# daughterboard.net
KiCad netlist of a schematic drawn in EAGLE
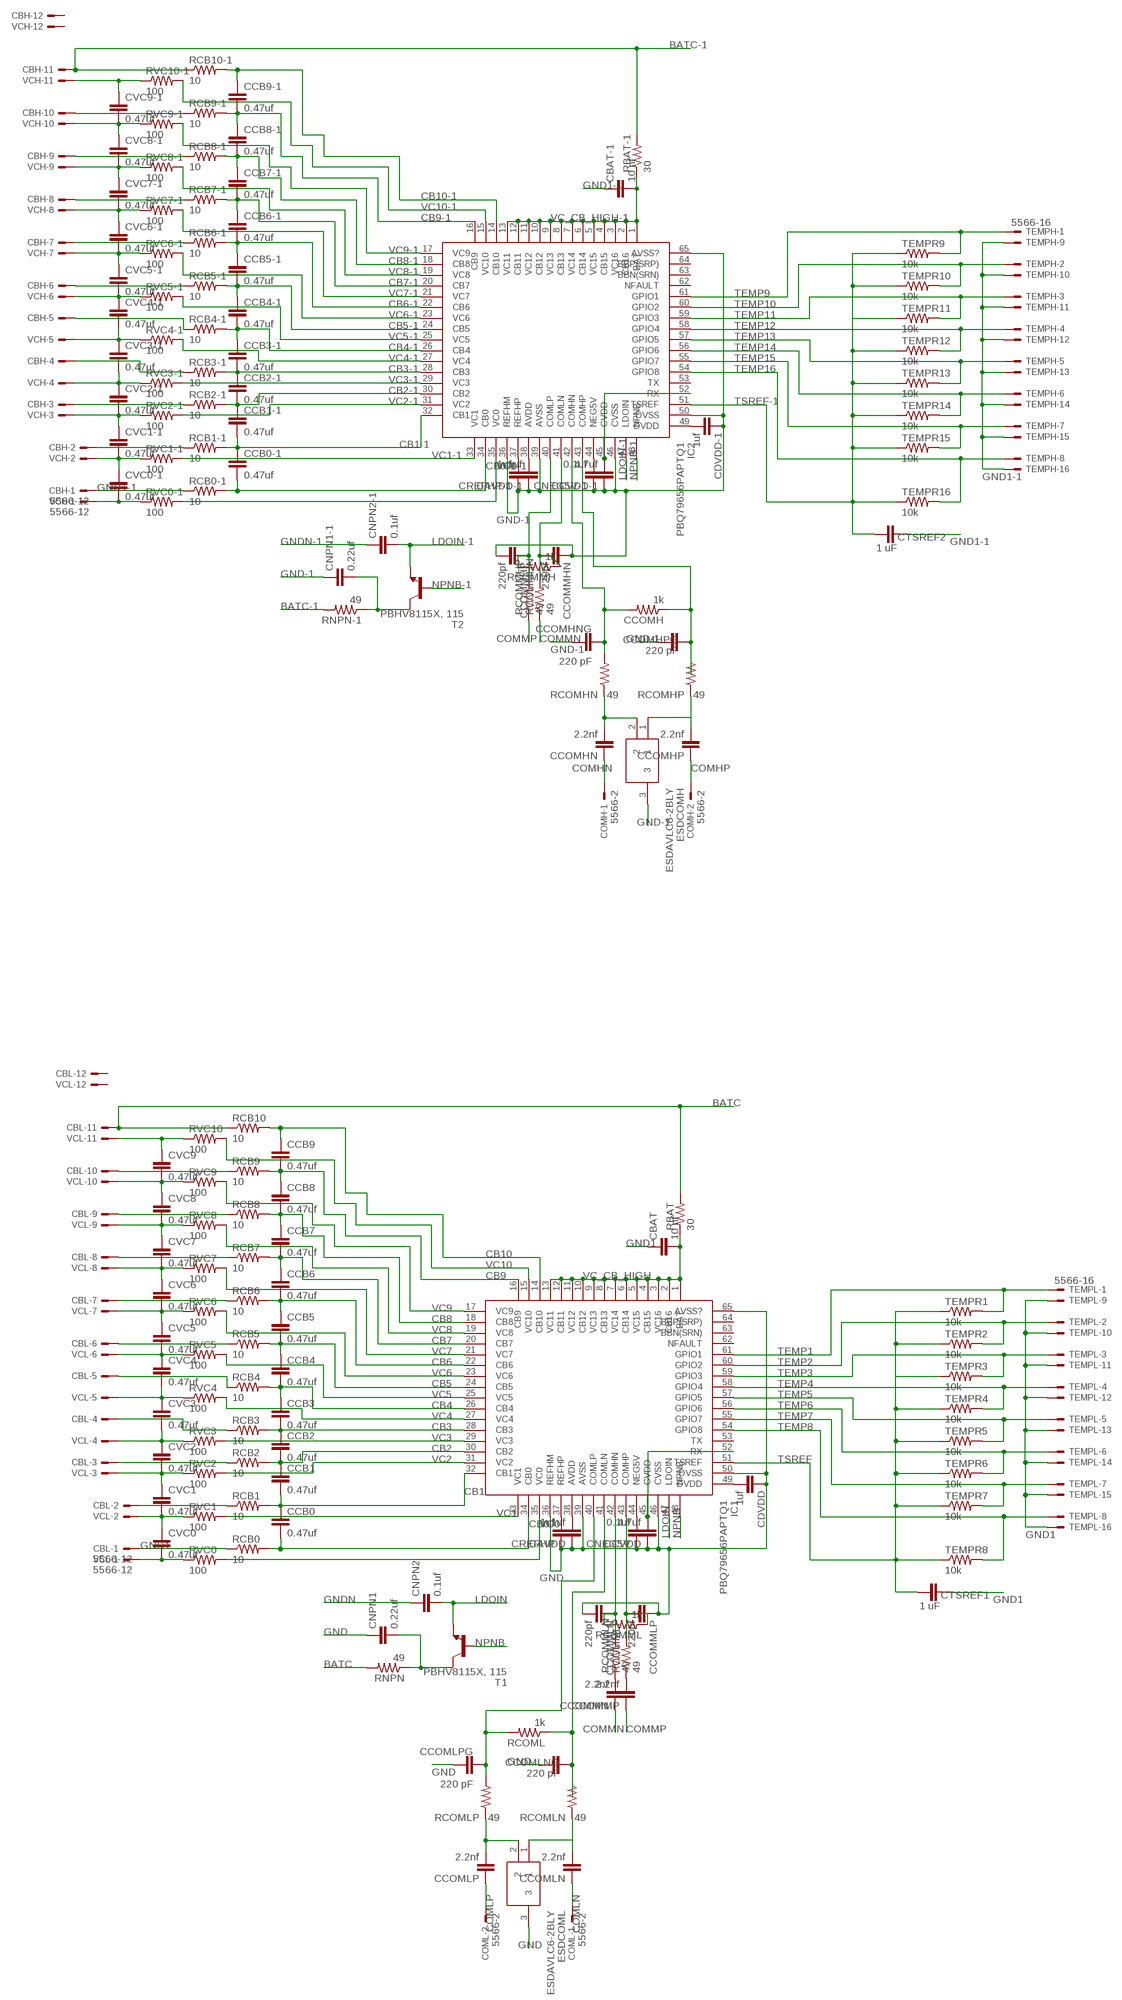
[diagram p0: schematic, sheet 1]

(export (version "E")
  (design (tool "Eeschema 10.0.6"))
  (components
    (comp (ref "CAVDD")
      (value "1uf")
      (footprint "eagle-import:C0603")
      (libsource (lib "eagle-import") (part "C-EUC0603"))
    )
    (comp (ref "CAVDD-1")
      (value "1uf")
      (footprint "eagle-import:C0603")
      (libsource (lib "eagle-import") (part "C-EUC0603"))
    )
    (comp (ref "CBAT")
      (value "10 nf")
      (footprint "eagle-import:C0603")
      (libsource (lib "eagle-import") (part "C-EUC0603"))
    )
    (comp (ref "CBAT-1")
      (value "10 nf")
      (footprint "eagle-import:C0603")
      (libsource (lib "eagle-import") (part "C-EUC0603"))
    )
    (comp (ref "CBH")
      (value "5566-12")
      (footprint "eagle-import:5566-12")
      (fields (field (name "MF") "MOLEX"))
      (libsource (lib "eagle-import") (part "5566-12"))
    )
    (comp (ref "CBL")
      (value "5566-12")
      (footprint "eagle-import:5566-12")
      (fields (field (name "MF") "MOLEX"))
      (libsource (lib "eagle-import") (part "5566-12"))
    )
    (comp (ref "CCB0")
      (value "0.47uf")
      (footprint "eagle-import:C0603")
      (libsource (lib "eagle-import") (part "C-EUC0603"))
    )
    (comp (ref "CCB0-1")
      (value "0.47uf")
      (footprint "eagle-import:C0603")
      (libsource (lib "eagle-import") (part "C-EUC0603"))
    )
    (comp (ref "CCB1")
      (value "0.47uf")
      (footprint "eagle-import:C0603")
      (libsource (lib "eagle-import") (part "C-EUC0603"))
    )
    (comp (ref "CCB1-1")
      (value "0.47uf")
      (footprint "eagle-import:C0603")
      (libsource (lib "eagle-import") (part "C-EUC0603"))
    )
    (comp (ref "CCB2")
      (value "0.47uf")
      (footprint "eagle-import:C0603")
      (libsource (lib "eagle-import") (part "C-EUC0603"))
    )
    (comp (ref "CCB2-1")
      (value "0.47uf")
      (footprint "eagle-import:C0603")
      (libsource (lib "eagle-import") (part "C-EUC0603"))
    )
    (comp (ref "CCB3")
      (value "0.47uf")
      (footprint "eagle-import:C0603")
      (libsource (lib "eagle-import") (part "C-EUC0603"))
    )
    (comp (ref "CCB3-1")
      (value "0.47uf")
      (footprint "eagle-import:C0603")
      (libsource (lib "eagle-import") (part "C-EUC0603"))
    )
    (comp (ref "CCB4")
      (value "0.47uf")
      (footprint "eagle-import:C0603")
      (libsource (lib "eagle-import") (part "C-EUC0603"))
    )
    (comp (ref "CCB4-1")
      (value "0.47uf")
      (footprint "eagle-import:C0603")
      (libsource (lib "eagle-import") (part "C-EUC0603"))
    )
    (comp (ref "CCB5")
      (value "0.47uf")
      (footprint "eagle-import:C0603")
      (libsource (lib "eagle-import") (part "C-EUC0603"))
    )
    (comp (ref "CCB5-1")
      (value "0.47uf")
      (footprint "eagle-import:C0603")
      (libsource (lib "eagle-import") (part "C-EUC0603"))
    )
    (comp (ref "CCB6")
      (value "0.47uf")
      (footprint "eagle-import:C0603")
      (libsource (lib "eagle-import") (part "C-EUC0603"))
    )
    (comp (ref "CCB6-1")
      (value "0.47uf")
      (footprint "eagle-import:C0603")
      (libsource (lib "eagle-import") (part "C-EUC0603"))
    )
    (comp (ref "CCB7")
      (value "0.47uf")
      (footprint "eagle-import:C0603")
      (libsource (lib "eagle-import") (part "C-EUC0603"))
    )
    (comp (ref "CCB7-1")
      (value "0.47uf")
      (footprint "eagle-import:C0603")
      (libsource (lib "eagle-import") (part "C-EUC0603"))
    )
    (comp (ref "CCB8")
      (value "0.47uf")
      (footprint "eagle-import:C0603")
      (libsource (lib "eagle-import") (part "C-EUC0603"))
    )
    (comp (ref "CCB8-1")
      (value "0.47uf")
      (footprint "eagle-import:C0603")
      (libsource (lib "eagle-import") (part "C-EUC0603"))
    )
    (comp (ref "CCB9")
      (value "0.47uf")
      (footprint "eagle-import:C0603")
      (libsource (lib "eagle-import") (part "C-EUC0603"))
    )
    (comp (ref "CCB9-1")
      (value "0.47uf")
      (footprint "eagle-import:C0603")
      (libsource (lib "eagle-import") (part "C-EUC0603"))
    )
    (comp (ref "CCOMH")
      (value "1k")
      (footprint "eagle-import:R0603")
      (libsource (lib "eagle-import") (part "R-US_R0603"))
    )
    (comp (ref "CCOMHN")
      (value "2.2nf")
      (footprint "eagle-import:C0603")
      (libsource (lib "eagle-import") (part "C-EUC0603"))
    )
    (comp (ref "CCOMHNG")
      (value "220 pF")
      (footprint "eagle-import:C0603")
      (libsource (lib "eagle-import") (part "C-EUC0603"))
    )
    (comp (ref "CCOMHP")
      (value "2.2nf")
      (footprint "eagle-import:C0603")
      (libsource (lib "eagle-import") (part "C-EUC0603"))
    )
    (comp (ref "CCOMHPG")
      (value "220 pF")
      (footprint "eagle-import:C0603")
      (libsource (lib "eagle-import") (part "C-EUC0603"))
    )
    (comp (ref "CCOMLN")
      (value "2.2nf")
      (footprint "eagle-import:C0603")
      (libsource (lib "eagle-import") (part "C-EUC0603"))
    )
    (comp (ref "CCOMLNG")
      (value "220 pF")
      (footprint "eagle-import:C0603")
      (libsource (lib "eagle-import") (part "C-EUC0603"))
    )
    (comp (ref "CCOMLP")
      (value "2.2nf")
      (footprint "eagle-import:C0603")
      (libsource (lib "eagle-import") (part "C-EUC0603"))
    )
    (comp (ref "CCOMLPG")
      (value "220 pF")
      (footprint "eagle-import:C0603")
      (libsource (lib "eagle-import") (part "C-EUC0603"))
    )
    (comp (ref "CCOMMHN")
      (value "220pf")
      (footprint "eagle-import:C0603")
      (libsource (lib "eagle-import") (part "C-EUC0603"))
    )
    (comp (ref "CCOMMHP")
      (value "220pf")
      (footprint "eagle-import:C0603")
      (libsource (lib "eagle-import") (part "C-EUC0603"))
    )
    (comp (ref "CCOMMLN")
      (value "220pf")
      (footprint "eagle-import:C0603")
      (libsource (lib "eagle-import") (part "C-EUC0603"))
    )
    (comp (ref "CCOMMLP")
      (value "220pf")
      (footprint "eagle-import:C0603")
      (libsource (lib "eagle-import") (part "C-EUC0603"))
    )
    (comp (ref "CCOMMN")
      (value "2.2nf")
      (footprint "eagle-import:C0603")
      (libsource (lib "eagle-import") (part "C-EUC0603"))
    )
    (comp (ref "CCOMMP")
      (value "2.2nf")
      (footprint "eagle-import:C0603")
      (libsource (lib "eagle-import") (part "C-EUC0603"))
    )
    (comp (ref "CCVDD")
      (value "4.7uf")
      (footprint "eagle-import:C0603")
      (libsource (lib "eagle-import") (part "C-EUC0603"))
    )
    (comp (ref "CCVDD-1")
      (value "4.7uf")
      (footprint "eagle-import:C0603")
      (libsource (lib "eagle-import") (part "C-EUC0603"))
    )
    (comp (ref "CDVDD")
      (value "1uf")
      (footprint "eagle-import:C0603")
      (libsource (lib "eagle-import") (part "C-EUC0603"))
    )
    (comp (ref "CDVDD-1")
      (value "1uf")
      (footprint "eagle-import:C0603")
      (libsource (lib "eagle-import") (part "C-EUC0603"))
    )
    (comp (ref "CNEG5V")
      (value "0.1uf")
      (footprint "eagle-import:C0603")
      (libsource (lib "eagle-import") (part "C-EUC0603"))
    )
    (comp (ref "CNEG5V-1")
      (value "0.1uf")
      (footprint "eagle-import:C0603")
      (libsource (lib "eagle-import") (part "C-EUC0603"))
    )
    (comp (ref "CNPN1")
      (value "0.22uf")
      (footprint "eagle-import:C0603")
      (libsource (lib "eagle-import") (part "C-EUC0603"))
    )
    (comp (ref "CNPN1-1")
      (value "0.22uf")
      (footprint "eagle-import:C0603")
      (libsource (lib "eagle-import") (part "C-EUC0603"))
    )
    (comp (ref "CNPN2")
      (value "0.1uf")
      (footprint "eagle-import:C0603")
      (libsource (lib "eagle-import") (part "C-EUC0603"))
    )
    (comp (ref "CNPN2-1")
      (value "0.1uf")
      (footprint "eagle-import:C0603")
      (libsource (lib "eagle-import") (part "C-EUC0603"))
    )
    (comp (ref "COMH")
      (value "5566-2")
      (footprint "eagle-import:5566-2")
      (fields (field (name "MF") "MOLEX"))
      (libsource (lib "eagle-import") (part "5566-2"))
    )
    (comp (ref "COML")
      (value "5566-2")
      (footprint "eagle-import:5566-2")
      (fields (field (name "MF") "MOLEX"))
      (libsource (lib "eagle-import") (part "5566-2"))
    )
    (comp (ref "CREFHP")
      (value "1uf")
      (footprint "eagle-import:C0603")
      (libsource (lib "eagle-import") (part "C-EUC0603"))
    )
    (comp (ref "CREFHP-1")
      (value "1uf")
      (footprint "eagle-import:C0603")
      (libsource (lib "eagle-import") (part "C-EUC0603"))
    )
    (comp (ref "CTSREF1")
      (value "1 uF")
      (footprint "eagle-import:C0603")
      (libsource (lib "eagle-import") (part "C-EUC0603"))
    )
    (comp (ref "CTSREF2")
      (value "1 uF")
      (footprint "eagle-import:C0603")
      (libsource (lib "eagle-import") (part "C-EUC0603"))
    )
    (comp (ref "CVC0")
      (value "0.47uf")
      (footprint "eagle-import:C0603")
      (libsource (lib "eagle-import") (part "C-EUC0603"))
    )
    (comp (ref "CVC0-1")
      (value "0.47uf")
      (footprint "eagle-import:C0603")
      (libsource (lib "eagle-import") (part "C-EUC0603"))
    )
    (comp (ref "CVC1")
      (value "0.47uf")
      (footprint "eagle-import:C0603")
      (libsource (lib "eagle-import") (part "C-EUC0603"))
    )
    (comp (ref "CVC1-1")
      (value "0.47uf")
      (footprint "eagle-import:C0603")
      (libsource (lib "eagle-import") (part "C-EUC0603"))
    )
    (comp (ref "CVC2")
      (value "0.47uf")
      (footprint "eagle-import:C0603")
      (libsource (lib "eagle-import") (part "C-EUC0603"))
    )
    (comp (ref "CVC2-1")
      (value "0.47uf")
      (footprint "eagle-import:C0603")
      (libsource (lib "eagle-import") (part "C-EUC0603"))
    )
    (comp (ref "CVC3")
      (value "0.47uf")
      (footprint "eagle-import:C0603")
      (libsource (lib "eagle-import") (part "C-EUC0603"))
    )
    (comp (ref "CVC3-1")
      (value "0.47uf")
      (footprint "eagle-import:C0603")
      (libsource (lib "eagle-import") (part "C-EUC0603"))
    )
    (comp (ref "CVC4")
      (value "0.47uf")
      (footprint "eagle-import:C0603")
      (libsource (lib "eagle-import") (part "C-EUC0603"))
    )
    (comp (ref "CVC4-1")
      (value "0.47uf")
      (footprint "eagle-import:C0603")
      (libsource (lib "eagle-import") (part "C-EUC0603"))
    )
    (comp (ref "CVC5")
      (value "0.47uf")
      (footprint "eagle-import:C0603")
      (libsource (lib "eagle-import") (part "C-EUC0603"))
    )
    (comp (ref "CVC5-1")
      (value "0.47uf")
      (footprint "eagle-import:C0603")
      (libsource (lib "eagle-import") (part "C-EUC0603"))
    )
    (comp (ref "CVC6")
      (value "0.47uf")
      (footprint "eagle-import:C0603")
      (libsource (lib "eagle-import") (part "C-EUC0603"))
    )
    (comp (ref "CVC6-1")
      (value "0.47uf")
      (footprint "eagle-import:C0603")
      (libsource (lib "eagle-import") (part "C-EUC0603"))
    )
    (comp (ref "CVC7")
      (value "0.47uf")
      (footprint "eagle-import:C0603")
      (libsource (lib "eagle-import") (part "C-EUC0603"))
    )
    (comp (ref "CVC7-1")
      (value "0.47uf")
      (footprint "eagle-import:C0603")
      (libsource (lib "eagle-import") (part "C-EUC0603"))
    )
    (comp (ref "CVC8")
      (value "0.47uf")
      (footprint "eagle-import:C0603")
      (libsource (lib "eagle-import") (part "C-EUC0603"))
    )
    (comp (ref "CVC8-1")
      (value "0.47uf")
      (footprint "eagle-import:C0603")
      (libsource (lib "eagle-import") (part "C-EUC0603"))
    )
    (comp (ref "CVC9")
      (value "0.47uf")
      (footprint "eagle-import:C0603")
      (libsource (lib "eagle-import") (part "C-EUC0603"))
    )
    (comp (ref "CVC9-1")
      (value "0.47uf")
      (footprint "eagle-import:C0603")
      (libsource (lib "eagle-import") (part "C-EUC0603"))
    )
    (comp (ref "ESDCOMH")
      (value "ESDAVLC6-2BLY")
      (footprint "eagle-import:SOT95P255X150-3N")
      (fields (field (name "MOUSER_PART_NUMBER") "511-ESDAVLC6-2BLY"))
      (libsource (lib "eagle-import") (part "ESDAVLC6-2BLY"))
    )
    (comp (ref "ESDCOML")
      (value "ESDAVLC6-2BLY")
      (footprint "eagle-import:SOT95P255X150-3N")
      (fields (field (name "MOUSER_PART_NUMBER") "511-ESDAVLC6-2BLY"))
      (libsource (lib "eagle-import") (part "ESDAVLC6-2BLY"))
    )
    (comp (ref "IC1")
      (value "PBQ79656PAPTQ1")
      (footprint "eagle-import:QFP50P1200X1200X120-65N")
      (libsource (lib "eagle-import") (part "PBQ79656PAPTQ1"))
    )
    (comp (ref "IC2")
      (value "PBQ79656PAPTQ1")
      (footprint "eagle-import:QFP50P1200X1200X120-65N")
      (libsource (lib "eagle-import") (part "PBQ79656PAPTQ1"))
    )
    (comp (ref "RBAT")
      (value "30")
      (footprint "eagle-import:R0603")
      (libsource (lib "eagle-import") (part "R-US_R0603"))
    )
    (comp (ref "RBAT-1")
      (value "30")
      (footprint "eagle-import:R0603")
      (libsource (lib "eagle-import") (part "R-US_R0603"))
    )
    (comp (ref "RCB0")
      (value "10")
      (footprint "eagle-import:R1210")
      (libsource (lib "eagle-import") (part "R-US_R1210"))
    )
    (comp (ref "RCB0-1")
      (value "10")
      (footprint "eagle-import:R1210")
      (libsource (lib "eagle-import") (part "R-US_R1210"))
    )
    (comp (ref "RCB1")
      (value "10")
      (footprint "eagle-import:R1210")
      (libsource (lib "eagle-import") (part "R-US_R1210"))
    )
    (comp (ref "RCB1-1")
      (value "10")
      (footprint "eagle-import:R1210")
      (libsource (lib "eagle-import") (part "R-US_R1210"))
    )
    (comp (ref "RCB2")
      (value "10")
      (footprint "eagle-import:R1210")
      (libsource (lib "eagle-import") (part "R-US_R1210"))
    )
    (comp (ref "RCB2-1")
      (value "10")
      (footprint "eagle-import:R1210")
      (libsource (lib "eagle-import") (part "R-US_R1210"))
    )
    (comp (ref "RCB3")
      (value "10")
      (footprint "eagle-import:R1210")
      (libsource (lib "eagle-import") (part "R-US_R1210"))
    )
    (comp (ref "RCB3-1")
      (value "10")
      (footprint "eagle-import:R1210")
      (libsource (lib "eagle-import") (part "R-US_R1210"))
    )
    (comp (ref "RCB4")
      (value "10")
      (footprint "eagle-import:R1210")
      (libsource (lib "eagle-import") (part "R-US_R1210"))
    )
    (comp (ref "RCB4-1")
      (value "10")
      (footprint "eagle-import:R1210")
      (libsource (lib "eagle-import") (part "R-US_R1210"))
    )
    (comp (ref "RCB5")
      (value "10")
      (footprint "eagle-import:R1210")
      (libsource (lib "eagle-import") (part "R-US_R1210"))
    )
    (comp (ref "RCB5-1")
      (value "10")
      (footprint "eagle-import:R1210")
      (libsource (lib "eagle-import") (part "R-US_R1210"))
    )
    (comp (ref "RCB6")
      (value "10")
      (footprint "eagle-import:R1210")
      (libsource (lib "eagle-import") (part "R-US_R1210"))
    )
    (comp (ref "RCB6-1")
      (value "10")
      (footprint "eagle-import:R1210")
      (libsource (lib "eagle-import") (part "R-US_R1210"))
    )
    (comp (ref "RCB7")
      (value "10")
      (footprint "eagle-import:R1210")
      (libsource (lib "eagle-import") (part "R-US_R1210"))
    )
    (comp (ref "RCB7-1")
      (value "10")
      (footprint "eagle-import:R1210")
      (libsource (lib "eagle-import") (part "R-US_R1210"))
    )
    (comp (ref "RCB8")
      (value "10")
      (footprint "eagle-import:R1210")
      (libsource (lib "eagle-import") (part "R-US_R1210"))
    )
    (comp (ref "RCB8-1")
      (value "10")
      (footprint "eagle-import:R1210")
      (libsource (lib "eagle-import") (part "R-US_R1210"))
    )
    (comp (ref "RCB9")
      (value "10")
      (footprint "eagle-import:R1210")
      (libsource (lib "eagle-import") (part "R-US_R1210"))
    )
    (comp (ref "RCB9-1")
      (value "10")
      (footprint "eagle-import:R1210")
      (libsource (lib "eagle-import") (part "R-US_R1210"))
    )
    (comp (ref "RCB10")
      (value "10")
      (footprint "eagle-import:R1210")
      (libsource (lib "eagle-import") (part "R-US_R1210"))
    )
    (comp (ref "RCB10-1")
      (value "10")
      (footprint "eagle-import:R1210")
      (libsource (lib "eagle-import") (part "R-US_R1210"))
    )
    (comp (ref "RCOMHN")
      (value "49")
      (footprint "eagle-import:R0603")
      (libsource (lib "eagle-import") (part "R-US_R0603"))
    )
    (comp (ref "RCOMHP")
      (value "49")
      (footprint "eagle-import:R0603")
      (libsource (lib "eagle-import") (part "R-US_R0603"))
    )
    (comp (ref "RCOML")
      (value "1k")
      (footprint "eagle-import:R0603")
      (libsource (lib "eagle-import") (part "R-US_R0603"))
    )
    (comp (ref "RCOMLN")
      (value "49")
      (footprint "eagle-import:R0603")
      (libsource (lib "eagle-import") (part "R-US_R0603"))
    )
    (comp (ref "RCOMLP")
      (value "49")
      (footprint "eagle-import:R0603")
      (libsource (lib "eagle-import") (part "R-US_R0603"))
    )
    (comp (ref "RCOMMH")
      (value "1k")
      (footprint "eagle-import:R0603")
      (libsource (lib "eagle-import") (part "R-US_R0603"))
    )
    (comp (ref "RCOMMHN")
      (value "49")
      (footprint "eagle-import:R0603")
      (libsource (lib "eagle-import") (part "R-US_R0603"))
    )
    (comp (ref "RCOMMHP")
      (value "49")
      (footprint "eagle-import:R0603")
      (libsource (lib "eagle-import") (part "R-US_R0603"))
    )
    (comp (ref "RCOMML")
      (value "1k")
      (footprint "eagle-import:R0603")
      (libsource (lib "eagle-import") (part "R-US_R0603"))
    )
    (comp (ref "RCOMMLN")
      (value "49")
      (footprint "eagle-import:R0603")
      (libsource (lib "eagle-import") (part "R-US_R0603"))
    )
    (comp (ref "RCOMMLP")
      (value "49")
      (footprint "eagle-import:R0603")
      (libsource (lib "eagle-import") (part "R-US_R0603"))
    )
    (comp (ref "RNPN")
      (value "49")
      (footprint "eagle-import:R0603")
      (libsource (lib "eagle-import") (part "R-US_R0603"))
    )
    (comp (ref "RNPN-1")
      (value "49")
      (footprint "eagle-import:R0603")
      (libsource (lib "eagle-import") (part "R-US_R0603"))
    )
    (comp (ref "RVC0")
      (value "100")
      (footprint "eagle-import:R0603")
      (libsource (lib "eagle-import") (part "R-US_R0603"))
    )
    (comp (ref "RVC0-1")
      (value "100")
      (footprint "eagle-import:R0603")
      (libsource (lib "eagle-import") (part "R-US_R0603"))
    )
    (comp (ref "RVC1")
      (value "100")
      (footprint "eagle-import:R0603")
      (libsource (lib "eagle-import") (part "R-US_R0603"))
    )
    (comp (ref "RVC1-1")
      (value "100")
      (footprint "eagle-import:R0603")
      (libsource (lib "eagle-import") (part "R-US_R0603"))
    )
    (comp (ref "RVC2")
      (value "100")
      (footprint "eagle-import:R0603")
      (libsource (lib "eagle-import") (part "R-US_R0603"))
    )
    (comp (ref "RVC2-1")
      (value "100")
      (footprint "eagle-import:R0603")
      (libsource (lib "eagle-import") (part "R-US_R0603"))
    )
    (comp (ref "RVC3")
      (value "100")
      (footprint "eagle-import:R0603")
      (libsource (lib "eagle-import") (part "R-US_R0603"))
    )
    (comp (ref "RVC3-1")
      (value "100")
      (footprint "eagle-import:R0603")
      (libsource (lib "eagle-import") (part "R-US_R0603"))
    )
    (comp (ref "RVC4")
      (value "100")
      (footprint "eagle-import:R0603")
      (libsource (lib "eagle-import") (part "R-US_R0603"))
    )
    (comp (ref "RVC4-1")
      (value "100")
      (footprint "eagle-import:R0603")
      (libsource (lib "eagle-import") (part "R-US_R0603"))
    )
    (comp (ref "RVC5")
      (value "100")
      (footprint "eagle-import:R0603")
      (libsource (lib "eagle-import") (part "R-US_R0603"))
    )
    (comp (ref "RVC5-1")
      (value "100")
      (footprint "eagle-import:R0603")
      (libsource (lib "eagle-import") (part "R-US_R0603"))
    )
    (comp (ref "RVC6")
      (value "100")
      (footprint "eagle-import:R0603")
      (libsource (lib "eagle-import") (part "R-US_R0603"))
    )
    (comp (ref "RVC6-1")
      (value "100")
      (footprint "eagle-import:R0603")
      (libsource (lib "eagle-import") (part "R-US_R0603"))
    )
    (comp (ref "RVC7")
      (value "100")
      (footprint "eagle-import:R0603")
      (libsource (lib "eagle-import") (part "R-US_R0603"))
    )
    (comp (ref "RVC7-1")
      (value "100")
      (footprint "eagle-import:R0603")
      (libsource (lib "eagle-import") (part "R-US_R0603"))
    )
    (comp (ref "RVC8")
      (value "100")
      (footprint "eagle-import:R0603")
      (libsource (lib "eagle-import") (part "R-US_R0603"))
    )
    (comp (ref "RVC8-1")
      (value "100")
      (footprint "eagle-import:R0603")
      (libsource (lib "eagle-import") (part "R-US_R0603"))
    )
    (comp (ref "RVC9")
      (value "100")
      (footprint "eagle-import:R0603")
      (libsource (lib "eagle-import") (part "R-US_R0603"))
    )
    (comp (ref "RVC9-1")
      (value "100")
      (footprint "eagle-import:R0603")
      (libsource (lib "eagle-import") (part "R-US_R0603"))
    )
    (comp (ref "RVC10")
      (value "100")
      (footprint "eagle-import:R0603")
      (libsource (lib "eagle-import") (part "R-US_R0603"))
    )
    (comp (ref "RVC10-1")
      (value "100")
      (footprint "eagle-import:R0603")
      (libsource (lib "eagle-import") (part "R-US_R0603"))
    )
    (comp (ref "T1")
      (value "PBHV8115X, 115")
      (footprint "eagle-import:SOT89-BCE")
      (libsource (lib "eagle-import") (part "-NPN-SOT89-BCEBC868"))
    )
    (comp (ref "T2")
      (value "PBHV8115X, 115")
      (footprint "eagle-import:SOT89-BCE")
      (libsource (lib "eagle-import") (part "-NPN-SOT89-BCEBC868"))
    )
    (comp (ref "TEMPH")
      (value "5566-16")
      (footprint "eagle-import:5566-16")
      (fields (field (name "MF") "MOLEX"))
      (libsource (lib "eagle-import") (part "5566-16"))
    )
    (comp (ref "TEMPL")
      (value "5566-16")
      (footprint "eagle-import:5566-16")
      (fields (field (name "MF") "MOLEX"))
      (libsource (lib "eagle-import") (part "5566-16"))
    )
    (comp (ref "TEMPR1")
      (value "10k")
      (footprint "eagle-import:R0603")
      (libsource (lib "eagle-import") (part "R-US_R0603"))
    )
    (comp (ref "TEMPR2")
      (value "10k")
      (footprint "eagle-import:R0603")
      (libsource (lib "eagle-import") (part "R-US_R0603"))
    )
    (comp (ref "TEMPR3")
      (value "10k")
      (footprint "eagle-import:R0603")
      (libsource (lib "eagle-import") (part "R-US_R0603"))
    )
    (comp (ref "TEMPR4")
      (value "10k")
      (footprint "eagle-import:R0603")
      (libsource (lib "eagle-import") (part "R-US_R0603"))
    )
    (comp (ref "TEMPR5")
      (value "10k")
      (footprint "eagle-import:R0603")
      (libsource (lib "eagle-import") (part "R-US_R0603"))
    )
    (comp (ref "TEMPR6")
      (value "10k")
      (footprint "eagle-import:R0603")
      (libsource (lib "eagle-import") (part "R-US_R0603"))
    )
    (comp (ref "TEMPR7")
      (value "10k")
      (footprint "eagle-import:R0603")
      (libsource (lib "eagle-import") (part "R-US_R0603"))
    )
    (comp (ref "TEMPR8")
      (value "10k")
      (footprint "eagle-import:R0603")
      (libsource (lib "eagle-import") (part "R-US_R0603"))
    )
    (comp (ref "TEMPR9")
      (value "10k")
      (footprint "eagle-import:R0603")
      (libsource (lib "eagle-import") (part "R-US_R0603"))
    )
    (comp (ref "TEMPR10")
      (value "10k")
      (footprint "eagle-import:R0603")
      (libsource (lib "eagle-import") (part "R-US_R0603"))
    )
    (comp (ref "TEMPR11")
      (value "10k")
      (footprint "eagle-import:R0603")
      (libsource (lib "eagle-import") (part "R-US_R0603"))
    )
    (comp (ref "TEMPR12")
      (value "10k")
      (footprint "eagle-import:R0603")
      (libsource (lib "eagle-import") (part "R-US_R0603"))
    )
    (comp (ref "TEMPR13")
      (value "10k")
      (footprint "eagle-import:R0603")
      (libsource (lib "eagle-import") (part "R-US_R0603"))
    )
    (comp (ref "TEMPR14")
      (value "10k")
      (footprint "eagle-import:R0603")
      (libsource (lib "eagle-import") (part "R-US_R0603"))
    )
    (comp (ref "TEMPR15")
      (value "10k")
      (footprint "eagle-import:R0603")
      (libsource (lib "eagle-import") (part "R-US_R0603"))
    )
    (comp (ref "TEMPR16")
      (value "10k")
      (footprint "eagle-import:R0603")
      (libsource (lib "eagle-import") (part "R-US_R0603"))
    )
    (comp (ref "VCH")
      (value "5566-12")
      (footprint "eagle-import:5566-12")
      (fields (field (name "MF") "MOLEX"))
      (libsource (lib "eagle-import") (part "5566-12"))
    )
    (comp (ref "VCL")
      (value "5566-12")
      (footprint "eagle-import:5566-12")
      (fields (field (name "MF") "MOLEX"))
      (libsource (lib "eagle-import") (part "5566-12"))
    )
  )
  (nets
    (net (code "1") (name "/BATC") (class "Default")
      (node (ref "CBL") (pin "11") (pinfunction "S_11") (pintype "passive"))
      (node (ref "RBAT") (pin "2") (pinfunction "2_2") (pintype "passive"))
      (node (ref "RCB10") (pin "1") (pinfunction "1_1") (pintype "passive"))
      (node (ref "RNPN") (pin "2") (pinfunction "2_2") (pintype "passive"))
    )
    (net (code "2") (name "/BATC-1") (class "Default")
      (node (ref "CBH") (pin "11") (pinfunction "S_11") (pintype "passive"))
      (node (ref "RBAT-1") (pin "2") (pinfunction "2_2") (pintype "passive"))
      (node (ref "RCB10-1") (pin "1") (pinfunction "1_1") (pintype "passive"))
      (node (ref "RNPN-1") (pin "2") (pinfunction "2_2") (pintype "passive"))
    )
    (net (code "3") (name "/CB0") (class "Default")
      (node (ref "CCB0") (pin "2") (pinfunction "2_2") (pintype "passive"))
      (node (ref "IC1") (pin "34") (pinfunction "CB0_34") (pintype "bidirectional"))
      (node (ref "RCB0") (pin "2") (pinfunction "2_2") (pintype "passive"))
    )
    (net (code "4") (name "/CB0-1") (class "Default")
      (node (ref "CCB0-1") (pin "2") (pinfunction "2_2") (pintype "passive"))
      (node (ref "IC2") (pin "34") (pinfunction "CB0_34") (pintype "bidirectional"))
      (node (ref "RCB0-1") (pin "2") (pinfunction "2_2") (pintype "passive"))
    )
    (net (code "5") (name "/CB1") (class "Default")
      (node (ref "CCB0") (pin "1") (pinfunction "1_1") (pintype "passive"))
      (node (ref "CCB1") (pin "2") (pinfunction "2_2") (pintype "passive"))
      (node (ref "IC1") (pin "32") (pinfunction "CB1_32") (pintype "bidirectional"))
      (node (ref "RCB1") (pin "2") (pinfunction "2_2") (pintype "passive"))
    )
    (net (code "6") (name "/CB1-1") (class "Default")
      (node (ref "CCB0-1") (pin "1") (pinfunction "1_1") (pintype "passive"))
      (node (ref "CCB1-1") (pin "2") (pinfunction "2_2") (pintype "passive"))
      (node (ref "IC2") (pin "32") (pinfunction "CB1_32") (pintype "bidirectional"))
      (node (ref "RCB1-1") (pin "2") (pinfunction "2_2") (pintype "passive"))
    )
    (net (code "7") (name "/CB2") (class "Default")
      (node (ref "CCB1") (pin "1") (pinfunction "1_1") (pintype "passive"))
      (node (ref "CCB2") (pin "2") (pinfunction "2_2") (pintype "passive"))
      (node (ref "IC1") (pin "30") (pinfunction "CB2_30") (pintype "bidirectional"))
      (node (ref "RCB2") (pin "2") (pinfunction "2_2") (pintype "passive"))
    )
    (net (code "8") (name "/CB2-1") (class "Default")
      (node (ref "CCB1-1") (pin "1") (pinfunction "1_1") (pintype "passive"))
      (node (ref "CCB2-1") (pin "2") (pinfunction "2_2") (pintype "passive"))
      (node (ref "IC2") (pin "30") (pinfunction "CB2_30") (pintype "bidirectional"))
      (node (ref "RCB2-1") (pin "2") (pinfunction "2_2") (pintype "passive"))
    )
    (net (code "9") (name "/CB3") (class "Default")
      (node (ref "CCB2") (pin "1") (pinfunction "1_1") (pintype "passive"))
      (node (ref "CCB3") (pin "2") (pinfunction "2_2") (pintype "passive"))
      (node (ref "IC1") (pin "28") (pinfunction "CB3_28") (pintype "bidirectional"))
      (node (ref "RCB3") (pin "2") (pinfunction "2_2") (pintype "passive"))
    )
    (net (code "10") (name "/CB3-1") (class "Default")
      (node (ref "CCB2-1") (pin "1") (pinfunction "1_1") (pintype "passive"))
      (node (ref "CCB3-1") (pin "2") (pinfunction "2_2") (pintype "passive"))
      (node (ref "IC2") (pin "28") (pinfunction "CB3_28") (pintype "bidirectional"))
      (node (ref "RCB3-1") (pin "2") (pinfunction "2_2") (pintype "passive"))
    )
    (net (code "11") (name "/CB4") (class "Default")
      (node (ref "CCB3") (pin "1") (pinfunction "1_1") (pintype "passive"))
      (node (ref "CCB4") (pin "2") (pinfunction "2_2") (pintype "passive"))
      (node (ref "IC1") (pin "26") (pinfunction "CB4_26") (pintype "bidirectional"))
      (node (ref "RCB4") (pin "2") (pinfunction "2_2") (pintype "passive"))
    )
    (net (code "12") (name "/CB4-1") (class "Default")
      (node (ref "CCB3-1") (pin "1") (pinfunction "1_1") (pintype "passive"))
      (node (ref "CCB4-1") (pin "2") (pinfunction "2_2") (pintype "passive"))
      (node (ref "IC2") (pin "26") (pinfunction "CB4_26") (pintype "bidirectional"))
      (node (ref "RCB4-1") (pin "2") (pinfunction "2_2") (pintype "passive"))
    )
    (net (code "13") (name "/CB5") (class "Default")
      (node (ref "CCB4") (pin "1") (pinfunction "1_1") (pintype "passive"))
      (node (ref "CCB5") (pin "2") (pinfunction "2_2") (pintype "passive"))
      (node (ref "IC1") (pin "24") (pinfunction "CB5_24") (pintype "bidirectional"))
      (node (ref "RCB5") (pin "2") (pinfunction "2_2") (pintype "passive"))
    )
    (net (code "14") (name "/CB5-1") (class "Default")
      (node (ref "CCB4-1") (pin "1") (pinfunction "1_1") (pintype "passive"))
      (node (ref "CCB5-1") (pin "2") (pinfunction "2_2") (pintype "passive"))
      (node (ref "IC2") (pin "24") (pinfunction "CB5_24") (pintype "bidirectional"))
      (node (ref "RCB5-1") (pin "2") (pinfunction "2_2") (pintype "passive"))
    )
    (net (code "15") (name "/CB6") (class "Default")
      (node (ref "CCB5") (pin "1") (pinfunction "1_1") (pintype "passive"))
      (node (ref "CCB6") (pin "2") (pinfunction "2_2") (pintype "passive"))
      (node (ref "IC1") (pin "22") (pinfunction "CB6_22") (pintype "bidirectional"))
      (node (ref "RCB6") (pin "2") (pinfunction "2_2") (pintype "passive"))
    )
    (net (code "16") (name "/CB6-1") (class "Default")
      (node (ref "CCB5-1") (pin "1") (pinfunction "1_1") (pintype "passive"))
      (node (ref "CCB6-1") (pin "2") (pinfunction "2_2") (pintype "passive"))
      (node (ref "IC2") (pin "22") (pinfunction "CB6_22") (pintype "bidirectional"))
      (node (ref "RCB6-1") (pin "2") (pinfunction "2_2") (pintype "passive"))
    )
    (net (code "17") (name "/CB7") (class "Default")
      (node (ref "CCB6") (pin "1") (pinfunction "1_1") (pintype "passive"))
      (node (ref "CCB7") (pin "2") (pinfunction "2_2") (pintype "passive"))
      (node (ref "IC1") (pin "20") (pinfunction "CB7_20") (pintype "bidirectional"))
      (node (ref "RCB7") (pin "2") (pinfunction "2_2") (pintype "passive"))
    )
    (net (code "18") (name "/CB7-1") (class "Default")
      (node (ref "CCB6-1") (pin "1") (pinfunction "1_1") (pintype "passive"))
      (node (ref "CCB7-1") (pin "2") (pinfunction "2_2") (pintype "passive"))
      (node (ref "IC2") (pin "20") (pinfunction "CB7_20") (pintype "bidirectional"))
      (node (ref "RCB7-1") (pin "2") (pinfunction "2_2") (pintype "passive"))
    )
    (net (code "19") (name "/CB8") (class "Default")
      (node (ref "CCB7") (pin "1") (pinfunction "1_1") (pintype "passive"))
      (node (ref "CCB8") (pin "2") (pinfunction "2_2") (pintype "passive"))
      (node (ref "IC1") (pin "18") (pinfunction "CB8_18") (pintype "bidirectional"))
      (node (ref "RCB8") (pin "2") (pinfunction "2_2") (pintype "passive"))
    )
    (net (code "20") (name "/CB8-1") (class "Default")
      (node (ref "CCB7-1") (pin "1") (pinfunction "1_1") (pintype "passive"))
      (node (ref "CCB8-1") (pin "2") (pinfunction "2_2") (pintype "passive"))
      (node (ref "IC2") (pin "18") (pinfunction "CB8_18") (pintype "bidirectional"))
      (node (ref "RCB8-1") (pin "2") (pinfunction "2_2") (pintype "passive"))
    )
    (net (code "21") (name "/CB9") (class "Default")
      (node (ref "CCB8") (pin "1") (pinfunction "1_1") (pintype "passive"))
      (node (ref "CCB9") (pin "2") (pinfunction "2_2") (pintype "passive"))
      (node (ref "IC1") (pin "16") (pinfunction "CB9_16") (pintype "bidirectional"))
      (node (ref "RCB9") (pin "2") (pinfunction "2_2") (pintype "passive"))
    )
    (net (code "22") (name "/CB9-1") (class "Default")
      (node (ref "CCB8-1") (pin "1") (pinfunction "1_1") (pintype "passive"))
      (node (ref "CCB9-1") (pin "2") (pinfunction "2_2") (pintype "passive"))
      (node (ref "IC2") (pin "16") (pinfunction "CB9_16") (pintype "bidirectional"))
      (node (ref "RCB9-1") (pin "2") (pinfunction "2_2") (pintype "passive"))
    )
    (net (code "23") (name "/CB10") (class "Default")
      (node (ref "CCB9") (pin "1") (pinfunction "1_1") (pintype "passive"))
      (node (ref "IC1") (pin "14") (pinfunction "CB10_14") (pintype "bidirectional"))
      (node (ref "RCB10") (pin "2") (pinfunction "2_2") (pintype "passive"))
    )
    (net (code "24") (name "/CB10-1") (class "Default")
      (node (ref "CCB9-1") (pin "1") (pinfunction "1_1") (pintype "passive"))
      (node (ref "IC2") (pin "14") (pinfunction "CB10_14") (pintype "bidirectional"))
      (node (ref "RCB10-1") (pin "2") (pinfunction "2_2") (pintype "passive"))
    )
    (net (code "25") (name "/COMHN") (class "Default")
      (node (ref "CCOMHN") (pin "1") (pinfunction "1_1") (pintype "passive"))
      (node (ref "COMH") (pin "1") (pinfunction "S_1") (pintype "passive"))
    )
    (net (code "26") (name "/COMHP") (class "Default")
      (node (ref "CCOMHP") (pin "1") (pinfunction "1_1") (pintype "passive"))
      (node (ref "COMH") (pin "2") (pinfunction "S_2") (pintype "passive"))
    )
    (net (code "27") (name "/COMLN") (class "Default")
      (node (ref "CCOMLN") (pin "1") (pinfunction "1_1") (pintype "passive"))
      (node (ref "COML") (pin "1") (pinfunction "S_1") (pintype "passive"))
    )
    (net (code "28") (name "/COMLP") (class "Default")
      (node (ref "CCOMLP") (pin "1") (pinfunction "1_1") (pintype "passive"))
      (node (ref "COML") (pin "2") (pinfunction "S_2") (pintype "passive"))
    )
    (net (code "29") (name "/COMMN") (class "Default")
      (node (ref "CCOMMN") (pin "1") (pinfunction "1_1") (pintype "passive"))
      (node (ref "RCOMMHN") (pin "1") (pinfunction "1_1") (pintype "passive"))
    )
    (net (code "30") (name "/COMMP") (class "Default")
      (node (ref "CCOMMP") (pin "1") (pinfunction "1_1") (pintype "passive"))
      (node (ref "RCOMMHP") (pin "1") (pinfunction "1_1") (pintype "passive"))
    )
    (net (code "31") (name "/GND") (class "Default")
      (node (ref "CAVDD") (pin "1") (pinfunction "1_1") (pintype "passive"))
      (node (ref "CCOMLNG") (pin "1") (pinfunction "1_1") (pintype "passive"))
      (node (ref "CCOMLPG") (pin "1") (pinfunction "1_1") (pintype "passive"))
      (node (ref "CCOMMLN") (pin "2") (pinfunction "2_2") (pintype "passive"))
      (node (ref "CCOMMLP") (pin "1") (pinfunction "1_1") (pintype "passive"))
      (node (ref "CCVDD") (pin "1") (pinfunction "1_1") (pintype "passive"))
      (node (ref "CDVDD") (pin "1") (pinfunction "1_1") (pintype "passive"))
      (node (ref "CNEG5V") (pin "1") (pinfunction "1_1") (pintype "passive"))
      (node (ref "CNPN1") (pin "1") (pinfunction "1_1") (pintype "passive"))
      (node (ref "CREFHP") (pin "1") (pinfunction "1_1") (pintype "passive"))
      (node (ref "ESDCOML") (pin "3") (pinfunction "3_3") (pintype "bidirectional"))
      (node (ref "IC1") (pin "36") (pinfunction "REFHM_36") (pintype "bidirectional"))
      (node (ref "IC1") (pin "39") (pinfunction "AVSS_39") (pintype "bidirectional"))
      (node (ref "IC1") (pin "46") (pinfunction "CVSS_46") (pintype "bidirectional"))
      (node (ref "IC1") (pin "50") (pinfunction "DVSS_50") (pintype "bidirectional"))
      (node (ref "IC1") (pin "65") (pinfunction "AVSS?_65") (pintype "bidirectional"))
    )
    (net (code "32") (name "/GND-1") (class "Default")
      (node (ref "CAVDD-1") (pin "1") (pinfunction "1_1") (pintype "passive"))
      (node (ref "CCOMHNG") (pin "1") (pinfunction "1_1") (pintype "passive"))
      (node (ref "CCOMHPG") (pin "1") (pinfunction "1_1") (pintype "passive"))
      (node (ref "CCOMMHN") (pin "1") (pinfunction "1_1") (pintype "passive"))
      (node (ref "CCOMMHP") (pin "2") (pinfunction "2_2") (pintype "passive"))
      (node (ref "CCVDD-1") (pin "1") (pinfunction "1_1") (pintype "passive"))
      (node (ref "CDVDD-1") (pin "1") (pinfunction "1_1") (pintype "passive"))
      (node (ref "CNEG5V-1") (pin "1") (pinfunction "1_1") (pintype "passive"))
      (node (ref "CNPN1-1") (pin "1") (pinfunction "1_1") (pintype "passive"))
      (node (ref "CREFHP-1") (pin "1") (pinfunction "1_1") (pintype "passive"))
      (node (ref "ESDCOMH") (pin "3") (pinfunction "3_3") (pintype "bidirectional"))
      (node (ref "IC2") (pin "36") (pinfunction "REFHM_36") (pintype "bidirectional"))
      (node (ref "IC2") (pin "39") (pinfunction "AVSS_39") (pintype "bidirectional"))
      (node (ref "IC2") (pin "46") (pinfunction "CVSS_46") (pintype "bidirectional"))
      (node (ref "IC2") (pin "50") (pinfunction "DVSS_50") (pintype "bidirectional"))
      (node (ref "IC2") (pin "65") (pinfunction "AVSS?_65") (pintype "bidirectional"))
    )
    (net (code "33") (name "/GND1") (class "Default")
      (node (ref "CBAT") (pin "1") (pinfunction "1_1") (pintype "passive"))
      (node (ref "CBL") (pin "1") (pinfunction "S_1") (pintype "passive"))
      (node (ref "CTSREF1") (pin "1") (pinfunction "1_1") (pintype "passive"))
      (node (ref "RCB0") (pin "1") (pinfunction "1_1") (pintype "passive"))
      (node (ref "TEMPL") (pin "10") (pinfunction "S_10") (pintype "passive"))
      (node (ref "TEMPL") (pin "11") (pinfunction "S_11") (pintype "passive"))
      (node (ref "TEMPL") (pin "12") (pinfunction "S_12") (pintype "passive"))
      (node (ref "TEMPL") (pin "13") (pinfunction "S_13") (pintype "passive"))
      (node (ref "TEMPL") (pin "14") (pinfunction "S_14") (pintype "passive"))
      (node (ref "TEMPL") (pin "15") (pinfunction "S_15") (pintype "passive"))
      (node (ref "TEMPL") (pin "16") (pinfunction "S_16") (pintype "passive"))
      (node (ref "TEMPL") (pin "9") (pinfunction "S_9") (pintype "passive"))
    )
    (net (code "34") (name "/GND1-1") (class "Default")
      (node (ref "CBAT-1") (pin "1") (pinfunction "1_1") (pintype "passive"))
      (node (ref "CBH") (pin "1") (pinfunction "S_1") (pintype "passive"))
      (node (ref "CTSREF2") (pin "1") (pinfunction "1_1") (pintype "passive"))
      (node (ref "RCB0-1") (pin "1") (pinfunction "1_1") (pintype "passive"))
      (node (ref "TEMPH") (pin "10") (pinfunction "S_10") (pintype "passive"))
      (node (ref "TEMPH") (pin "11") (pinfunction "S_11") (pintype "passive"))
      (node (ref "TEMPH") (pin "12") (pinfunction "S_12") (pintype "passive"))
      (node (ref "TEMPH") (pin "13") (pinfunction "S_13") (pintype "passive"))
      (node (ref "TEMPH") (pin "14") (pinfunction "S_14") (pintype "passive"))
      (node (ref "TEMPH") (pin "15") (pinfunction "S_15") (pintype "passive"))
      (node (ref "TEMPH") (pin "16") (pinfunction "S_16") (pintype "passive"))
      (node (ref "TEMPH") (pin "9") (pinfunction "S_9") (pintype "passive"))
    )
    (net (code "35") (name "/GNDN") (class "Default")
      (node (ref "CNPN2") (pin "1") (pinfunction "1_1") (pintype "passive"))
    )
    (net (code "36") (name "/GNDN-1") (class "Default")
      (node (ref "CNPN2-1") (pin "1") (pinfunction "1_1") (pintype "passive"))
    )
    (net (code "37") (name "/LDOIN") (class "Default")
      (node (ref "CNPN2") (pin "2") (pinfunction "2_2") (pintype "passive"))
      (node (ref "IC1") (pin "47") (pinfunction "LDOIN_47") (pintype "bidirectional"))
      (node (ref "T1") (pin "E") (pinfunction "E_E") (pintype "passive"))
    )
    (net (code "38") (name "/LDOIN-1") (class "Default")
      (node (ref "CNPN2-1") (pin "2") (pinfunction "2_2") (pintype "passive"))
      (node (ref "IC2") (pin "47") (pinfunction "LDOIN_47") (pintype "bidirectional"))
      (node (ref "T2") (pin "E") (pinfunction "E_E") (pintype "passive"))
    )
    (net (code "39") (name "/NPNB") (class "Default")
      (node (ref "IC1") (pin "48") (pinfunction "NPNB_48") (pintype "bidirectional"))
      (node (ref "T1") (pin "B") (pinfunction "B_B") (pintype "passive"))
    )
    (net (code "40") (name "/NPNB-1") (class "Default")
      (node (ref "IC2") (pin "48") (pinfunction "NPNB_48") (pintype "bidirectional"))
      (node (ref "T2") (pin "B") (pinfunction "B_B") (pintype "passive"))
    )
    (net (code "41") (name "/TEMP1") (class "Default")
      (node (ref "IC1") (pin "61") (pinfunction "GPIO1_61") (pintype "bidirectional"))
      (node (ref "TEMPL") (pin "1") (pinfunction "S_1") (pintype "passive"))
      (node (ref "TEMPR1") (pin "2") (pinfunction "2_2") (pintype "passive"))
    )
    (net (code "42") (name "/TEMP2") (class "Default")
      (node (ref "IC1") (pin "60") (pinfunction "GPIO2_60") (pintype "bidirectional"))
      (node (ref "TEMPL") (pin "2") (pinfunction "S_2") (pintype "passive"))
      (node (ref "TEMPR2") (pin "2") (pinfunction "2_2") (pintype "passive"))
    )
    (net (code "43") (name "/TEMP3") (class "Default")
      (node (ref "IC1") (pin "59") (pinfunction "GPIO3_59") (pintype "bidirectional"))
      (node (ref "TEMPL") (pin "3") (pinfunction "S_3") (pintype "passive"))
      (node (ref "TEMPR3") (pin "2") (pinfunction "2_2") (pintype "passive"))
    )
    (net (code "44") (name "/TEMP4") (class "Default")
      (node (ref "IC1") (pin "58") (pinfunction "GPIO4_58") (pintype "bidirectional"))
      (node (ref "TEMPL") (pin "4") (pinfunction "S_4") (pintype "passive"))
      (node (ref "TEMPR4") (pin "2") (pinfunction "2_2") (pintype "passive"))
    )
    (net (code "45") (name "/TEMP5") (class "Default")
      (node (ref "IC1") (pin "57") (pinfunction "GPIO5_57") (pintype "bidirectional"))
      (node (ref "TEMPL") (pin "5") (pinfunction "S_5") (pintype "passive"))
      (node (ref "TEMPR5") (pin "2") (pinfunction "2_2") (pintype "passive"))
    )
    (net (code "46") (name "/TEMP6") (class "Default")
      (node (ref "IC1") (pin "56") (pinfunction "GPIO6_56") (pintype "bidirectional"))
      (node (ref "TEMPL") (pin "6") (pinfunction "S_6") (pintype "passive"))
      (node (ref "TEMPR6") (pin "2") (pinfunction "2_2") (pintype "passive"))
    )
    (net (code "47") (name "/TEMP7") (class "Default")
      (node (ref "IC1") (pin "55") (pinfunction "GPIO7_55") (pintype "bidirectional"))
      (node (ref "TEMPL") (pin "7") (pinfunction "S_7") (pintype "passive"))
      (node (ref "TEMPR7") (pin "2") (pinfunction "2_2") (pintype "passive"))
    )
    (net (code "48") (name "/TEMP8") (class "Default")
      (node (ref "IC1") (pin "54") (pinfunction "GPIO8_54") (pintype "bidirectional"))
      (node (ref "TEMPL") (pin "8") (pinfunction "S_8") (pintype "passive"))
      (node (ref "TEMPR8") (pin "2") (pinfunction "2_2") (pintype "passive"))
    )
    (net (code "49") (name "/TEMP9") (class "Default")
      (node (ref "IC2") (pin "61") (pinfunction "GPIO1_61") (pintype "bidirectional"))
      (node (ref "TEMPH") (pin "1") (pinfunction "S_1") (pintype "passive"))
      (node (ref "TEMPR9") (pin "2") (pinfunction "2_2") (pintype "passive"))
    )
    (net (code "50") (name "/TEMP10") (class "Default")
      (node (ref "IC2") (pin "60") (pinfunction "GPIO2_60") (pintype "bidirectional"))
      (node (ref "TEMPH") (pin "2") (pinfunction "S_2") (pintype "passive"))
      (node (ref "TEMPR10") (pin "2") (pinfunction "2_2") (pintype "passive"))
    )
    (net (code "51") (name "/TEMP11") (class "Default")
      (node (ref "IC2") (pin "59") (pinfunction "GPIO3_59") (pintype "bidirectional"))
      (node (ref "TEMPH") (pin "3") (pinfunction "S_3") (pintype "passive"))
      (node (ref "TEMPR11") (pin "2") (pinfunction "2_2") (pintype "passive"))
    )
    (net (code "52") (name "/TEMP12") (class "Default")
      (node (ref "IC2") (pin "58") (pinfunction "GPIO4_58") (pintype "bidirectional"))
      (node (ref "TEMPH") (pin "4") (pinfunction "S_4") (pintype "passive"))
      (node (ref "TEMPR12") (pin "2") (pinfunction "2_2") (pintype "passive"))
    )
    (net (code "53") (name "/TEMP13") (class "Default")
      (node (ref "IC2") (pin "57") (pinfunction "GPIO5_57") (pintype "bidirectional"))
      (node (ref "TEMPH") (pin "5") (pinfunction "S_5") (pintype "passive"))
      (node (ref "TEMPR13") (pin "2") (pinfunction "2_2") (pintype "passive"))
    )
    (net (code "54") (name "/TEMP14") (class "Default")
      (node (ref "IC2") (pin "56") (pinfunction "GPIO6_56") (pintype "bidirectional"))
      (node (ref "TEMPH") (pin "6") (pinfunction "S_6") (pintype "passive"))
      (node (ref "TEMPR14") (pin "2") (pinfunction "2_2") (pintype "passive"))
    )
    (net (code "55") (name "/TEMP15") (class "Default")
      (node (ref "IC2") (pin "55") (pinfunction "GPIO7_55") (pintype "bidirectional"))
      (node (ref "TEMPH") (pin "7") (pinfunction "S_7") (pintype "passive"))
      (node (ref "TEMPR15") (pin "2") (pinfunction "2_2") (pintype "passive"))
    )
    (net (code "56") (name "/TEMP16") (class "Default")
      (node (ref "IC2") (pin "54") (pinfunction "GPIO8_54") (pintype "bidirectional"))
      (node (ref "TEMPH") (pin "8") (pinfunction "S_8") (pintype "passive"))
      (node (ref "TEMPR16") (pin "2") (pinfunction "2_2") (pintype "passive"))
    )
    (net (code "57") (name "/TSREF") (class "Default")
      (node (ref "CTSREF1") (pin "2") (pinfunction "2_2") (pintype "passive"))
      (node (ref "IC1") (pin "51") (pinfunction "TSREF_51") (pintype "bidirectional"))
      (node (ref "TEMPR1") (pin "1") (pinfunction "1_1") (pintype "passive"))
      (node (ref "TEMPR2") (pin "1") (pinfunction "1_1") (pintype "passive"))
      (node (ref "TEMPR3") (pin "1") (pinfunction "1_1") (pintype "passive"))
      (node (ref "TEMPR4") (pin "1") (pinfunction "1_1") (pintype "passive"))
      (node (ref "TEMPR5") (pin "1") (pinfunction "1_1") (pintype "passive"))
      (node (ref "TEMPR6") (pin "1") (pinfunction "1_1") (pintype "passive"))
      (node (ref "TEMPR7") (pin "1") (pinfunction "1_1") (pintype "passive"))
      (node (ref "TEMPR8") (pin "1") (pinfunction "1_1") (pintype "passive"))
    )
    (net (code "58") (name "/TSREF-1") (class "Default")
      (node (ref "CTSREF2") (pin "2") (pinfunction "2_2") (pintype "passive"))
      (node (ref "IC2") (pin "51") (pinfunction "TSREF_51") (pintype "bidirectional"))
      (node (ref "TEMPR10") (pin "1") (pinfunction "1_1") (pintype "passive"))
      (node (ref "TEMPR11") (pin "1") (pinfunction "1_1") (pintype "passive"))
      (node (ref "TEMPR12") (pin "1") (pinfunction "1_1") (pintype "passive"))
      (node (ref "TEMPR13") (pin "1") (pinfunction "1_1") (pintype "passive"))
      (node (ref "TEMPR14") (pin "1") (pinfunction "1_1") (pintype "passive"))
      (node (ref "TEMPR15") (pin "1") (pinfunction "1_1") (pintype "passive"))
      (node (ref "TEMPR16") (pin "1") (pinfunction "1_1") (pintype "passive"))
      (node (ref "TEMPR9") (pin "1") (pinfunction "1_1") (pintype "passive"))
    )
    (net (code "59") (name "/VC0") (class "Default")
      (node (ref "IC1") (pin "35") (pinfunction "VC0_35") (pintype "bidirectional"))
      (node (ref "RVC0") (pin "2") (pinfunction "2_2") (pintype "passive"))
    )
    (net (code "60") (name "/VC0-1") (class "Default")
      (node (ref "IC2") (pin "35") (pinfunction "VC0_35") (pintype "bidirectional"))
      (node (ref "RVC0-1") (pin "2") (pinfunction "2_2") (pintype "passive"))
    )
    (net (code "61") (name "/VC1") (class "Default")
      (node (ref "IC1") (pin "33") (pinfunction "VC1_33") (pintype "bidirectional"))
      (node (ref "RVC1") (pin "2") (pinfunction "2_2") (pintype "passive"))
    )
    (net (code "62") (name "/VC1-1") (class "Default")
      (node (ref "IC2") (pin "33") (pinfunction "VC1_33") (pintype "bidirectional"))
      (node (ref "RVC1-1") (pin "2") (pinfunction "2_2") (pintype "passive"))
    )
    (net (code "63") (name "/VC2") (class "Default")
      (node (ref "IC1") (pin "31") (pinfunction "VC2_31") (pintype "bidirectional"))
      (node (ref "RVC2") (pin "2") (pinfunction "2_2") (pintype "passive"))
    )
    (net (code "64") (name "/VC2-1") (class "Default")
      (node (ref "IC2") (pin "31") (pinfunction "VC2_31") (pintype "bidirectional"))
      (node (ref "RVC2-1") (pin "2") (pinfunction "2_2") (pintype "passive"))
    )
    (net (code "65") (name "/VC3") (class "Default")
      (node (ref "IC1") (pin "29") (pinfunction "VC3_29") (pintype "bidirectional"))
      (node (ref "RVC3") (pin "2") (pinfunction "2_2") (pintype "passive"))
    )
    (net (code "66") (name "/VC3-1") (class "Default")
      (node (ref "IC2") (pin "29") (pinfunction "VC3_29") (pintype "bidirectional"))
      (node (ref "RVC3-1") (pin "2") (pinfunction "2_2") (pintype "passive"))
    )
    (net (code "67") (name "/VC4") (class "Default")
      (node (ref "IC1") (pin "27") (pinfunction "VC4_27") (pintype "bidirectional"))
      (node (ref "RVC4") (pin "2") (pinfunction "2_2") (pintype "passive"))
    )
    (net (code "68") (name "/VC4-1") (class "Default")
      (node (ref "IC2") (pin "27") (pinfunction "VC4_27") (pintype "bidirectional"))
      (node (ref "RVC4-1") (pin "2") (pinfunction "2_2") (pintype "passive"))
    )
    (net (code "69") (name "/VC5") (class "Default")
      (node (ref "IC1") (pin "25") (pinfunction "VC5_25") (pintype "bidirectional"))
      (node (ref "RVC5") (pin "2") (pinfunction "2_2") (pintype "passive"))
    )
    (net (code "70") (name "/VC5-1") (class "Default")
      (node (ref "IC2") (pin "25") (pinfunction "VC5_25") (pintype "bidirectional"))
      (node (ref "RVC5-1") (pin "2") (pinfunction "2_2") (pintype "passive"))
    )
    (net (code "71") (name "/VC6") (class "Default")
      (node (ref "IC1") (pin "23") (pinfunction "VC6_23") (pintype "bidirectional"))
      (node (ref "RVC6") (pin "2") (pinfunction "2_2") (pintype "passive"))
    )
    (net (code "72") (name "/VC6-1") (class "Default")
      (node (ref "IC2") (pin "23") (pinfunction "VC6_23") (pintype "bidirectional"))
      (node (ref "RVC6-1") (pin "2") (pinfunction "2_2") (pintype "passive"))
    )
    (net (code "73") (name "/VC7") (class "Default")
      (node (ref "IC1") (pin "21") (pinfunction "VC7_21") (pintype "bidirectional"))
      (node (ref "RVC7") (pin "2") (pinfunction "2_2") (pintype "passive"))
    )
    (net (code "74") (name "/VC7-1") (class "Default")
      (node (ref "IC2") (pin "21") (pinfunction "VC7_21") (pintype "bidirectional"))
      (node (ref "RVC7-1") (pin "2") (pinfunction "2_2") (pintype "passive"))
    )
    (net (code "75") (name "/VC8") (class "Default")
      (node (ref "IC1") (pin "19") (pinfunction "VC8_19") (pintype "bidirectional"))
      (node (ref "RVC8") (pin "2") (pinfunction "2_2") (pintype "passive"))
    )
    (net (code "76") (name "/VC8-1") (class "Default")
      (node (ref "IC2") (pin "19") (pinfunction "VC8_19") (pintype "bidirectional"))
      (node (ref "RVC8-1") (pin "2") (pinfunction "2_2") (pintype "passive"))
    )
    (net (code "77") (name "/VC9") (class "Default")
      (node (ref "IC1") (pin "17") (pinfunction "VC9_17") (pintype "bidirectional"))
      (node (ref "RVC9") (pin "2") (pinfunction "2_2") (pintype "passive"))
    )
    (net (code "78") (name "/VC9-1") (class "Default")
      (node (ref "IC2") (pin "17") (pinfunction "VC9_17") (pintype "bidirectional"))
      (node (ref "RVC9-1") (pin "2") (pinfunction "2_2") (pintype "passive"))
    )
    (net (code "79") (name "/VC10") (class "Default")
      (node (ref "IC1") (pin "15") (pinfunction "VC10_15") (pintype "bidirectional"))
      (node (ref "RVC10") (pin "2") (pinfunction "2_2") (pintype "passive"))
    )
    (net (code "80") (name "/VC10-1") (class "Default")
      (node (ref "IC2") (pin "15") (pinfunction "VC10_15") (pintype "bidirectional"))
      (node (ref "RVC10-1") (pin "2") (pinfunction "2_2") (pintype "passive"))
    )
    (net (code "81") (name "/VC_CB_HIGH") (class "Default")
      (node (ref "CBAT") (pin "2") (pinfunction "2_2") (pintype "passive"))
      (node (ref "IC1") (pin "1") (pinfunction "BAT_1") (pintype "bidirectional"))
      (node (ref "IC1") (pin "10") (pinfunction "CB12_10") (pintype "bidirectional"))
      (node (ref "IC1") (pin "11") (pinfunction "VC12_11") (pintype "bidirectional"))
      (node (ref "IC1") (pin "12") (pinfunction "CB11_12") (pintype "bidirectional"))
      (node (ref "IC1") (pin "13") (pinfunction "VC11_13") (pintype "bidirectional"))
      (node (ref "IC1") (pin "2") (pinfunction "CB16_2") (pintype "bidirectional"))
      (node (ref "IC1") (pin "3") (pinfunction "VC16_3") (pintype "bidirectional"))
      (node (ref "IC1") (pin "4") (pinfunction "CB15_4") (pintype "bidirectional"))
      (node (ref "IC1") (pin "5") (pinfunction "VC15_5") (pintype "bidirectional"))
      (node (ref "IC1") (pin "6") (pinfunction "CB14_6") (pintype "bidirectional"))
      (node (ref "IC1") (pin "7") (pinfunction "VC14_7") (pintype "bidirectional"))
      (node (ref "IC1") (pin "8") (pinfunction "CB13_8") (pintype "bidirectional"))
      (node (ref "IC1") (pin "9") (pinfunction "VC13_9") (pintype "bidirectional"))
      (node (ref "RBAT") (pin "1") (pinfunction "1_1") (pintype "passive"))
    )
    (net (code "82") (name "/VC_CB_HIGH-1") (class "Default")
      (node (ref "CBAT-1") (pin "2") (pinfunction "2_2") (pintype "passive"))
      (node (ref "IC2") (pin "1") (pinfunction "BAT_1") (pintype "bidirectional"))
      (node (ref "IC2") (pin "10") (pinfunction "CB12_10") (pintype "bidirectional"))
      (node (ref "IC2") (pin "11") (pinfunction "VC12_11") (pintype "bidirectional"))
      (node (ref "IC2") (pin "12") (pinfunction "CB11_12") (pintype "bidirectional"))
      (node (ref "IC2") (pin "13") (pinfunction "VC11_13") (pintype "bidirectional"))
      (node (ref "IC2") (pin "2") (pinfunction "CB16_2") (pintype "bidirectional"))
      (node (ref "IC2") (pin "3") (pinfunction "VC16_3") (pintype "bidirectional"))
      (node (ref "IC2") (pin "4") (pinfunction "CB15_4") (pintype "bidirectional"))
      (node (ref "IC2") (pin "5") (pinfunction "VC15_5") (pintype "bidirectional"))
      (node (ref "IC2") (pin "6") (pinfunction "CB14_6") (pintype "bidirectional"))
      (node (ref "IC2") (pin "7") (pinfunction "VC14_7") (pintype "bidirectional"))
      (node (ref "IC2") (pin "8") (pinfunction "CB13_8") (pintype "bidirectional"))
      (node (ref "IC2") (pin "9") (pinfunction "VC13_9") (pintype "bidirectional"))
      (node (ref "RBAT-1") (pin "1") (pinfunction "1_1") (pintype "passive"))
    )
    (net (code "83") (name "Net-(CBHB-S)") (class "Default")
      (node (ref "CBH") (pin "10") (pinfunction "S_10") (pintype "passive"))
      (node (ref "RCB9-1") (pin "1") (pinfunction "1_1") (pintype "passive"))
    )
    (net (code "84") (name "Net-(CBHE-S)") (class "Default")
      (node (ref "CBH") (pin "2") (pinfunction "S_2") (pintype "passive"))
      (node (ref "RCB1-1") (pin "1") (pinfunction "1_1") (pintype "passive"))
    )
    (net (code "85") (name "Net-(CBHF-S)") (class "Default")
      (node (ref "CBH") (pin "3") (pinfunction "S_3") (pintype "passive"))
      (node (ref "RCB2-1") (pin "1") (pinfunction "1_1") (pintype "passive"))
    )
    (net (code "86") (name "Net-(CBHG-S)") (class "Default")
      (node (ref "CBH") (pin "4") (pinfunction "S_4") (pintype "passive"))
      (node (ref "RCB3-1") (pin "1") (pinfunction "1_1") (pintype "passive"))
    )
    (net (code "87") (name "Net-(CBHH-S)") (class "Default")
      (node (ref "CBH") (pin "5") (pinfunction "S_5") (pintype "passive"))
      (node (ref "RCB4-1") (pin "1") (pinfunction "1_1") (pintype "passive"))
    )
    (net (code "88") (name "Net-(CBHI-S)") (class "Default")
      (node (ref "CBH") (pin "6") (pinfunction "S_6") (pintype "passive"))
      (node (ref "RCB5-1") (pin "1") (pinfunction "1_1") (pintype "passive"))
    )
    (net (code "89") (name "Net-(CBHJ-S)") (class "Default")
      (node (ref "CBH") (pin "7") (pinfunction "S_7") (pintype "passive"))
      (node (ref "RCB6-1") (pin "1") (pinfunction "1_1") (pintype "passive"))
    )
    (net (code "90") (name "Net-(CBHK-S)") (class "Default")
      (node (ref "CBH") (pin "8") (pinfunction "S_8") (pintype "passive"))
      (node (ref "RCB7-1") (pin "1") (pinfunction "1_1") (pintype "passive"))
    )
    (net (code "91") (name "Net-(CBHL-S)") (class "Default")
      (node (ref "CBH") (pin "9") (pinfunction "S_9") (pintype "passive"))
      (node (ref "RCB8-1") (pin "1") (pinfunction "1_1") (pintype "passive"))
    )
    (net (code "92") (name "Net-(CBLB-S)") (class "Default")
      (node (ref "CBL") (pin "10") (pinfunction "S_10") (pintype "passive"))
      (node (ref "RCB9") (pin "1") (pinfunction "1_1") (pintype "passive"))
    )
    (net (code "93") (name "Net-(CBLE-S)") (class "Default")
      (node (ref "CBL") (pin "2") (pinfunction "S_2") (pintype "passive"))
      (node (ref "RCB1") (pin "1") (pinfunction "1_1") (pintype "passive"))
    )
    (net (code "94") (name "Net-(CBLF-S)") (class "Default")
      (node (ref "CBL") (pin "3") (pinfunction "S_3") (pintype "passive"))
      (node (ref "RCB2") (pin "1") (pinfunction "1_1") (pintype "passive"))
    )
    (net (code "95") (name "Net-(CBLG-S)") (class "Default")
      (node (ref "CBL") (pin "4") (pinfunction "S_4") (pintype "passive"))
      (node (ref "RCB3") (pin "1") (pinfunction "1_1") (pintype "passive"))
    )
    (net (code "96") (name "Net-(CBLH-S)") (class "Default")
      (node (ref "CBL") (pin "5") (pinfunction "S_5") (pintype "passive"))
      (node (ref "RCB4") (pin "1") (pinfunction "1_1") (pintype "passive"))
    )
    (net (code "97") (name "Net-(CBLI-S)") (class "Default")
      (node (ref "CBL") (pin "6") (pinfunction "S_6") (pintype "passive"))
      (node (ref "RCB5") (pin "1") (pinfunction "1_1") (pintype "passive"))
    )
    (net (code "98") (name "Net-(CBLJ-S)") (class "Default")
      (node (ref "CBL") (pin "7") (pinfunction "S_7") (pintype "passive"))
      (node (ref "RCB6") (pin "1") (pinfunction "1_1") (pintype "passive"))
    )
    (net (code "99") (name "Net-(CBLK-S)") (class "Default")
      (node (ref "CBL") (pin "8") (pinfunction "S_8") (pintype "passive"))
      (node (ref "RCB7") (pin "1") (pinfunction "1_1") (pintype "passive"))
    )
    (net (code "100") (name "Net-(CBLL-S)") (class "Default")
      (node (ref "CBL") (pin "9") (pinfunction "S_9") (pintype "passive"))
      (node (ref "RCB8") (pin "1") (pinfunction "1_1") (pintype "passive"))
    )
    (net (code "101") (name "Net-(CCOMHN-Pad2)") (class "Default")
      (node (ref "CCOMHN") (pin "2") (pinfunction "2_2") (pintype "passive"))
      (node (ref "ESDCOMH") (pin "2") (pinfunction "2_2") (pintype "bidirectional"))
      (node (ref "RCOMHN") (pin "1") (pinfunction "1_1") (pintype "passive"))
    )
    (net (code "102") (name "Net-(CCOMHP-Pad2)") (class "Default")
      (node (ref "CCOMHP") (pin "2") (pinfunction "2_2") (pintype "passive"))
      (node (ref "ESDCOMH") (pin "1") (pinfunction "1_1") (pintype "bidirectional"))
      (node (ref "RCOMHP") (pin "1") (pinfunction "1_1") (pintype "passive"))
    )
    (net (code "103") (name "Net-(CCOMLN-Pad2)") (class "Default")
      (node (ref "CCOMLN") (pin "2") (pinfunction "2_2") (pintype "passive"))
      (node (ref "ESDCOML") (pin "1") (pinfunction "1_1") (pintype "bidirectional"))
      (node (ref "RCOMLN") (pin "1") (pinfunction "1_1") (pintype "passive"))
    )
    (net (code "104") (name "Net-(CCOMLP-Pad2)") (class "Default")
      (node (ref "CCOMLP") (pin "2") (pinfunction "2_2") (pintype "passive"))
      (node (ref "ESDCOML") (pin "2") (pinfunction "2_2") (pintype "bidirectional"))
      (node (ref "RCOMLP") (pin "1") (pinfunction "1_1") (pintype "passive"))
    )
    (net (code "105") (name "Net-(CCOMMN-Pad2)") (class "Default")
      (node (ref "CCOMMN") (pin "2") (pinfunction "2_2") (pintype "passive"))
      (node (ref "RCOMMLN") (pin "1") (pinfunction "1_1") (pintype "passive"))
    )
    (net (code "106") (name "Net-(CCOMMP-Pad2)") (class "Default")
      (node (ref "CCOMMP") (pin "2") (pinfunction "2_2") (pintype "passive"))
      (node (ref "RCOMMLP") (pin "1") (pinfunction "1_1") (pintype "passive"))
    )
    (net (code "107") (name "Net-(CNPN1-1-Pad2)") (class "Default")
      (node (ref "CNPN1-1") (pin "2") (pinfunction "2_2") (pintype "passive"))
      (node (ref "RNPN-1") (pin "1") (pinfunction "1_1") (pintype "passive"))
      (node (ref "T2") (pin "C") (pinfunction "C_C") (pintype "passive"))
    )
    (net (code "108") (name "Net-(CNPN1-Pad2)") (class "Default")
      (node (ref "CNPN1") (pin "2") (pinfunction "2_2") (pintype "passive"))
      (node (ref "RNPN") (pin "1") (pinfunction "1_1") (pintype "passive"))
      (node (ref "T1") (pin "C") (pinfunction "C_C") (pintype "passive"))
    )
    (net (code "109") (name "Net-(IC1-AVDD)") (class "Default")
      (node (ref "CAVDD") (pin "2") (pinfunction "2_2") (pintype "passive"))
      (node (ref "IC1") (pin "38") (pinfunction "AVDD_38") (pintype "bidirectional"))
    )
    (net (code "110") (name "Net-(IC1-COMHN)") (class "Default")
      (node (ref "CCOMMLN") (pin "1") (pinfunction "1_1") (pintype "passive"))
      (node (ref "IC1") (pin "42") (pinfunction "COMHN_42") (pintype "bidirectional"))
      (node (ref "RCOMML") (pin "2") (pinfunction "2_2") (pintype "passive"))
      (node (ref "RCOMMLN") (pin "2") (pinfunction "2_2") (pintype "passive"))
    )
    (net (code "111") (name "Net-(IC1-COMHP)") (class "Default")
      (node (ref "CCOMMLP") (pin "2") (pinfunction "2_2") (pintype "passive"))
      (node (ref "IC1") (pin "43") (pinfunction "COMHP_43") (pintype "bidirectional"))
      (node (ref "RCOMML") (pin "1") (pinfunction "1_1") (pintype "passive"))
      (node (ref "RCOMMLP") (pin "2") (pinfunction "2_2") (pintype "passive"))
    )
    (net (code "112") (name "Net-(IC1-COMLN)") (class "Default")
      (node (ref "CCOMLNG") (pin "2") (pinfunction "2_2") (pintype "passive"))
      (node (ref "IC1") (pin "41") (pinfunction "COMLN_41") (pintype "bidirectional"))
      (node (ref "RCOML") (pin "1") (pinfunction "1_1") (pintype "passive"))
      (node (ref "RCOMLN") (pin "2") (pinfunction "2_2") (pintype "passive"))
    )
    (net (code "113") (name "Net-(IC1-COMLP)") (class "Default")
      (node (ref "CCOMLPG") (pin "2") (pinfunction "2_2") (pintype "passive"))
      (node (ref "IC1") (pin "40") (pinfunction "COMLP_40") (pintype "bidirectional"))
      (node (ref "RCOML") (pin "2") (pinfunction "2_2") (pintype "passive"))
      (node (ref "RCOMLP") (pin "2") (pinfunction "2_2") (pintype "passive"))
    )
    (net (code "114") (name "Net-(IC1-CVDD)") (class "Default")
      (node (ref "CCVDD") (pin "2") (pinfunction "2_2") (pintype "passive"))
      (node (ref "IC1") (pin "45") (pinfunction "CVDD_45") (pintype "bidirectional"))
      (node (ref "IC1") (pin "52") (pinfunction "RX_52") (pintype "bidirectional"))
    )
    (net (code "115") (name "Net-(IC1-DVDD)") (class "Default")
      (node (ref "CDVDD") (pin "2") (pinfunction "2_2") (pintype "passive"))
      (node (ref "IC1") (pin "49") (pinfunction "DVDD_49") (pintype "bidirectional"))
    )
    (net (code "116") (name "Net-(IC1-NEG5V)") (class "Default")
      (node (ref "CNEG5V") (pin "2") (pinfunction "2_2") (pintype "passive"))
      (node (ref "IC1") (pin "44") (pinfunction "NEG5V_44") (pintype "bidirectional"))
    )
    (net (code "117") (name "Net-(IC1-REFHP)") (class "Default")
      (node (ref "CREFHP") (pin "2") (pinfunction "2_2") (pintype "passive"))
      (node (ref "IC1") (pin "37") (pinfunction "REFHP_37") (pintype "bidirectional"))
    )
    (net (code "118") (name "Net-(IC2-AVDD)") (class "Default")
      (node (ref "CAVDD-1") (pin "2") (pinfunction "2_2") (pintype "passive"))
      (node (ref "IC2") (pin "38") (pinfunction "AVDD_38") (pintype "bidirectional"))
    )
    (net (code "119") (name "Net-(IC2-COMHN)") (class "Default")
      (node (ref "CCOMH") (pin "2") (pinfunction "2_2") (pintype "passive"))
      (node (ref "CCOMHNG") (pin "2") (pinfunction "2_2") (pintype "passive"))
      (node (ref "IC2") (pin "42") (pinfunction "COMHN_42") (pintype "bidirectional"))
      (node (ref "RCOMHN") (pin "2") (pinfunction "2_2") (pintype "passive"))
    )
    (net (code "120") (name "Net-(IC2-COMHP)") (class "Default")
      (node (ref "CCOMH") (pin "1") (pinfunction "1_1") (pintype "passive"))
      (node (ref "CCOMHPG") (pin "2") (pinfunction "2_2") (pintype "passive"))
      (node (ref "IC2") (pin "43") (pinfunction "COMHP_43") (pintype "bidirectional"))
      (node (ref "RCOMHP") (pin "2") (pinfunction "2_2") (pintype "passive"))
    )
    (net (code "121") (name "Net-(IC2-COMLN)") (class "Default")
      (node (ref "CCOMMHN") (pin "2") (pinfunction "2_2") (pintype "passive"))
      (node (ref "IC2") (pin "41") (pinfunction "COMLN_41") (pintype "bidirectional"))
      (node (ref "RCOMMH") (pin "1") (pinfunction "1_1") (pintype "passive"))
      (node (ref "RCOMMHN") (pin "2") (pinfunction "2_2") (pintype "passive"))
    )
    (net (code "122") (name "Net-(IC2-COMLP)") (class "Default")
      (node (ref "CCOMMHP") (pin "1") (pinfunction "1_1") (pintype "passive"))
      (node (ref "IC2") (pin "40") (pinfunction "COMLP_40") (pintype "bidirectional"))
      (node (ref "RCOMMH") (pin "2") (pinfunction "2_2") (pintype "passive"))
      (node (ref "RCOMMHP") (pin "2") (pinfunction "2_2") (pintype "passive"))
    )
    (net (code "123") (name "Net-(IC2-CVDD)") (class "Default")
      (node (ref "CCVDD-1") (pin "2") (pinfunction "2_2") (pintype "passive"))
      (node (ref "IC2") (pin "45") (pinfunction "CVDD_45") (pintype "bidirectional"))
      (node (ref "IC2") (pin "52") (pinfunction "RX_52") (pintype "bidirectional"))
    )
    (net (code "124") (name "Net-(IC2-DVDD)") (class "Default")
      (node (ref "CDVDD-1") (pin "2") (pinfunction "2_2") (pintype "passive"))
      (node (ref "IC2") (pin "49") (pinfunction "DVDD_49") (pintype "bidirectional"))
    )
    (net (code "125") (name "Net-(IC2-NEG5V)") (class "Default")
      (node (ref "CNEG5V-1") (pin "2") (pinfunction "2_2") (pintype "passive"))
      (node (ref "IC2") (pin "44") (pinfunction "NEG5V_44") (pintype "bidirectional"))
    )
    (net (code "126") (name "Net-(IC2-REFHP)") (class "Default")
      (node (ref "CREFHP-1") (pin "2") (pinfunction "2_2") (pintype "passive"))
      (node (ref "IC2") (pin "37") (pinfunction "REFHP_37") (pintype "bidirectional"))
    )
    (net (code "127") (name "Net-(VCHA-S)") (class "Default")
      (node (ref "CVC0-1") (pin "2") (pinfunction "2_2") (pintype "passive"))
      (node (ref "RVC0-1") (pin "1") (pinfunction "1_1") (pintype "passive"))
      (node (ref "VCH") (pin "1") (pinfunction "S_1") (pintype "passive"))
    )
    (net (code "128") (name "Net-(VCHB-S)") (class "Default")
      (node (ref "CVC8-1") (pin "1") (pinfunction "1_1") (pintype "passive"))
      (node (ref "CVC9-1") (pin "2") (pinfunction "2_2") (pintype "passive"))
      (node (ref "RVC9-1") (pin "1") (pinfunction "1_1") (pintype "passive"))
      (node (ref "VCH") (pin "10") (pinfunction "S_10") (pintype "passive"))
    )
    (net (code "129") (name "Net-(VCHC-S)") (class "Default")
      (node (ref "CVC9-1") (pin "1") (pinfunction "1_1") (pintype "passive"))
      (node (ref "RVC10-1") (pin "1") (pinfunction "1_1") (pintype "passive"))
      (node (ref "VCH") (pin "11") (pinfunction "S_11") (pintype "passive"))
    )
    (net (code "130") (name "Net-(VCHE-S)") (class "Default")
      (node (ref "CVC0-1") (pin "1") (pinfunction "1_1") (pintype "passive"))
      (node (ref "CVC1-1") (pin "2") (pinfunction "2_2") (pintype "passive"))
      (node (ref "RVC1-1") (pin "1") (pinfunction "1_1") (pintype "passive"))
      (node (ref "VCH") (pin "2") (pinfunction "S_2") (pintype "passive"))
    )
    (net (code "131") (name "Net-(VCHF-S)") (class "Default")
      (node (ref "CVC1-1") (pin "1") (pinfunction "1_1") (pintype "passive"))
      (node (ref "CVC2-1") (pin "2") (pinfunction "2_2") (pintype "passive"))
      (node (ref "RVC2-1") (pin "1") (pinfunction "1_1") (pintype "passive"))
      (node (ref "VCH") (pin "3") (pinfunction "S_3") (pintype "passive"))
    )
    (net (code "132") (name "Net-(VCHG-S)") (class "Default")
      (node (ref "CVC2-1") (pin "1") (pinfunction "1_1") (pintype "passive"))
      (node (ref "CVC3-1") (pin "2") (pinfunction "2_2") (pintype "passive"))
      (node (ref "RVC3-1") (pin "1") (pinfunction "1_1") (pintype "passive"))
      (node (ref "VCH") (pin "4") (pinfunction "S_4") (pintype "passive"))
    )
    (net (code "133") (name "Net-(VCHH-S)") (class "Default")
      (node (ref "CVC3-1") (pin "1") (pinfunction "1_1") (pintype "passive"))
      (node (ref "CVC4-1") (pin "2") (pinfunction "2_2") (pintype "passive"))
      (node (ref "RVC4-1") (pin "1") (pinfunction "1_1") (pintype "passive"))
      (node (ref "VCH") (pin "5") (pinfunction "S_5") (pintype "passive"))
    )
    (net (code "134") (name "Net-(VCHI-S)") (class "Default")
      (node (ref "CVC4-1") (pin "1") (pinfunction "1_1") (pintype "passive"))
      (node (ref "CVC5-1") (pin "2") (pinfunction "2_2") (pintype "passive"))
      (node (ref "RVC5-1") (pin "1") (pinfunction "1_1") (pintype "passive"))
      (node (ref "VCH") (pin "6") (pinfunction "S_6") (pintype "passive"))
    )
    (net (code "135") (name "Net-(VCHJ-S)") (class "Default")
      (node (ref "CVC5-1") (pin "1") (pinfunction "1_1") (pintype "passive"))
      (node (ref "CVC6-1") (pin "2") (pinfunction "2_2") (pintype "passive"))
      (node (ref "RVC6-1") (pin "1") (pinfunction "1_1") (pintype "passive"))
      (node (ref "VCH") (pin "7") (pinfunction "S_7") (pintype "passive"))
    )
    (net (code "136") (name "Net-(VCHK-S)") (class "Default")
      (node (ref "CVC6-1") (pin "1") (pinfunction "1_1") (pintype "passive"))
      (node (ref "CVC7-1") (pin "2") (pinfunction "2_2") (pintype "passive"))
      (node (ref "RVC7-1") (pin "1") (pinfunction "1_1") (pintype "passive"))
      (node (ref "VCH") (pin "8") (pinfunction "S_8") (pintype "passive"))
    )
    (net (code "137") (name "Net-(VCHL-S)") (class "Default")
      (node (ref "CVC7-1") (pin "1") (pinfunction "1_1") (pintype "passive"))
      (node (ref "CVC8-1") (pin "2") (pinfunction "2_2") (pintype "passive"))
      (node (ref "RVC8-1") (pin "1") (pinfunction "1_1") (pintype "passive"))
      (node (ref "VCH") (pin "9") (pinfunction "S_9") (pintype "passive"))
    )
    (net (code "138") (name "Net-(VCLA-S)") (class "Default")
      (node (ref "CVC0") (pin "2") (pinfunction "2_2") (pintype "passive"))
      (node (ref "RVC0") (pin "1") (pinfunction "1_1") (pintype "passive"))
      (node (ref "VCL") (pin "1") (pinfunction "S_1") (pintype "passive"))
    )
    (net (code "139") (name "Net-(VCLB-S)") (class "Default")
      (node (ref "CVC8") (pin "1") (pinfunction "1_1") (pintype "passive"))
      (node (ref "CVC9") (pin "2") (pinfunction "2_2") (pintype "passive"))
      (node (ref "RVC9") (pin "1") (pinfunction "1_1") (pintype "passive"))
      (node (ref "VCL") (pin "10") (pinfunction "S_10") (pintype "passive"))
    )
    (net (code "140") (name "Net-(VCLC-S)") (class "Default")
      (node (ref "CVC9") (pin "1") (pinfunction "1_1") (pintype "passive"))
      (node (ref "RVC10") (pin "1") (pinfunction "1_1") (pintype "passive"))
      (node (ref "VCL") (pin "11") (pinfunction "S_11") (pintype "passive"))
    )
    (net (code "141") (name "Net-(VCLE-S)") (class "Default")
      (node (ref "CVC0") (pin "1") (pinfunction "1_1") (pintype "passive"))
      (node (ref "CVC1") (pin "2") (pinfunction "2_2") (pintype "passive"))
      (node (ref "RVC1") (pin "1") (pinfunction "1_1") (pintype "passive"))
      (node (ref "VCL") (pin "2") (pinfunction "S_2") (pintype "passive"))
    )
    (net (code "142") (name "Net-(VCLF-S)") (class "Default")
      (node (ref "CVC1") (pin "1") (pinfunction "1_1") (pintype "passive"))
      (node (ref "CVC2") (pin "2") (pinfunction "2_2") (pintype "passive"))
      (node (ref "RVC2") (pin "1") (pinfunction "1_1") (pintype "passive"))
      (node (ref "VCL") (pin "3") (pinfunction "S_3") (pintype "passive"))
    )
    (net (code "143") (name "Net-(VCLG-S)") (class "Default")
      (node (ref "CVC2") (pin "1") (pinfunction "1_1") (pintype "passive"))
      (node (ref "CVC3") (pin "2") (pinfunction "2_2") (pintype "passive"))
      (node (ref "RVC3") (pin "1") (pinfunction "1_1") (pintype "passive"))
      (node (ref "VCL") (pin "4") (pinfunction "S_4") (pintype "passive"))
    )
    (net (code "144") (name "Net-(VCLH-S)") (class "Default")
      (node (ref "CVC3") (pin "1") (pinfunction "1_1") (pintype "passive"))
      (node (ref "CVC4") (pin "2") (pinfunction "2_2") (pintype "passive"))
      (node (ref "RVC4") (pin "1") (pinfunction "1_1") (pintype "passive"))
      (node (ref "VCL") (pin "5") (pinfunction "S_5") (pintype "passive"))
    )
    (net (code "145") (name "Net-(VCLI-S)") (class "Default")
      (node (ref "CVC4") (pin "1") (pinfunction "1_1") (pintype "passive"))
      (node (ref "CVC5") (pin "2") (pinfunction "2_2") (pintype "passive"))
      (node (ref "RVC5") (pin "1") (pinfunction "1_1") (pintype "passive"))
      (node (ref "VCL") (pin "6") (pinfunction "S_6") (pintype "passive"))
    )
    (net (code "146") (name "Net-(VCLJ-S)") (class "Default")
      (node (ref "CVC5") (pin "1") (pinfunction "1_1") (pintype "passive"))
      (node (ref "CVC6") (pin "2") (pinfunction "2_2") (pintype "passive"))
      (node (ref "RVC6") (pin "1") (pinfunction "1_1") (pintype "passive"))
      (node (ref "VCL") (pin "7") (pinfunction "S_7") (pintype "passive"))
    )
    (net (code "147") (name "Net-(VCLK-S)") (class "Default")
      (node (ref "CVC6") (pin "1") (pinfunction "1_1") (pintype "passive"))
      (node (ref "CVC7") (pin "2") (pinfunction "2_2") (pintype "passive"))
      (node (ref "RVC7") (pin "1") (pinfunction "1_1") (pintype "passive"))
      (node (ref "VCL") (pin "8") (pinfunction "S_8") (pintype "passive"))
    )
    (net (code "148") (name "Net-(VCLL-S)") (class "Default")
      (node (ref "CVC7") (pin "1") (pinfunction "1_1") (pintype "passive"))
      (node (ref "CVC8") (pin "2") (pinfunction "2_2") (pintype "passive"))
      (node (ref "RVC8") (pin "1") (pinfunction "1_1") (pintype "passive"))
      (node (ref "VCL") (pin "9") (pinfunction "S_9") (pintype "passive"))
    )
    (net (code "149") (name "unconnected-(CBHD-S-Pad12)") (class "Default")
      (node (ref "CBH") (pin "12") (pinfunction "S_12") (pintype "passive"))
    )
    (net (code "150") (name "unconnected-(CBLD-S-Pad12)") (class "Default")
      (node (ref "CBL") (pin "12") (pinfunction "S_12") (pintype "passive"))
    )
    (net (code "151") (name "unconnected-(IC1-BBN(SRN)-Pad63)") (class "Default")
      (node (ref "IC1") (pin "63") (pinfunction "BBN(SRN)_63") (pintype "bidirectional"))
    )
    (net (code "152") (name "unconnected-(IC1-BBP(SRP)-Pad64)") (class "Default")
      (node (ref "IC1") (pin "64") (pinfunction "BBP(SRP)_64") (pintype "bidirectional"))
    )
    (net (code "153") (name "unconnected-(IC1-NFAULT-Pad62)") (class "Default")
      (node (ref "IC1") (pin "62") (pinfunction "NFAULT_62") (pintype "bidirectional"))
    )
    (net (code "154") (name "unconnected-(IC1-TX-Pad53)") (class "Default")
      (node (ref "IC1") (pin "53") (pinfunction "TX_53") (pintype "bidirectional"))
    )
    (net (code "155") (name "unconnected-(IC2-BBN(SRN)-Pad63)") (class "Default")
      (node (ref "IC2") (pin "63") (pinfunction "BBN(SRN)_63") (pintype "bidirectional"))
    )
    (net (code "156") (name "unconnected-(IC2-BBP(SRP)-Pad64)") (class "Default")
      (node (ref "IC2") (pin "64") (pinfunction "BBP(SRP)_64") (pintype "bidirectional"))
    )
    (net (code "157") (name "unconnected-(IC2-NFAULT-Pad62)") (class "Default")
      (node (ref "IC2") (pin "62") (pinfunction "NFAULT_62") (pintype "bidirectional"))
    )
    (net (code "158") (name "unconnected-(IC2-TX-Pad53)") (class "Default")
      (node (ref "IC2") (pin "53") (pinfunction "TX_53") (pintype "bidirectional"))
    )
    (net (code "159") (name "unconnected-(VCHD-S-Pad12)") (class "Default")
      (node (ref "VCH") (pin "12") (pinfunction "S_12") (pintype "passive"))
    )
    (net (code "160") (name "unconnected-(VCLD-S-Pad12)") (class "Default")
      (node (ref "VCL") (pin "12") (pinfunction "S_12") (pintype "passive"))
    )
  )
)
